# 555_timer.net
KiCad netlist of a schematic drawn in EAGLE
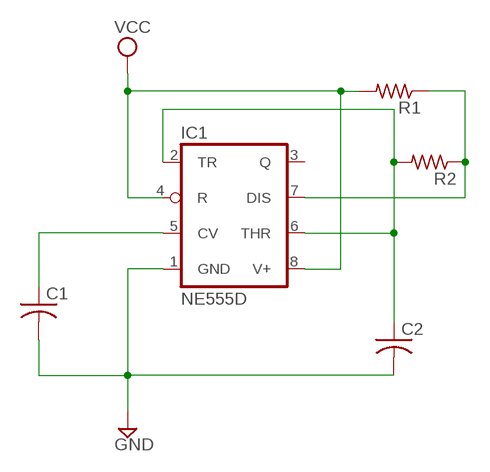
[diagram p0: schematic, sheet 1]

(export (version "E")
  (design (tool "Eeschema 10.0.6"))
  (components
    (comp (ref "C1")
      (value "C-USC0805")
      (footprint "eagle-import:C0805")
      (libsource (lib "eagle-import") (part "C-USC0805"))
    )
    (comp (ref "C2")
      (value "C-USC0805")
      (footprint "eagle-import:C0805")
      (libsource (lib "eagle-import") (part "C-USC0805"))
    )
    (comp (ref "IC1")
      (value "NE555D")
      (footprint "eagle-import:SO08")
      (libsource (lib "eagle-import") (part "555DNE"))
    )
    (comp (ref "R1")
      (value "R-US_R0805")
      (footprint "eagle-import:R0805")
      (libsource (lib "eagle-import") (part "R-US_R0805"))
    )
    (comp (ref "R2")
      (value "R-US_R0805")
      (footprint "eagle-import:R0805")
      (libsource (lib "eagle-import") (part "R-US_R0805"))
    )
  )
  (nets
    (net (code "1") (name "GND") (class "Default")
      (node (ref "C1") (pin "2") (pinfunction "2_2") (pintype "passive"))
      (node (ref "C2") (pin "2") (pinfunction "2_2") (pintype "passive"))
      (node (ref "IC1") (pin "1") (pinfunction "GND_1") (pintype "power_in"))
    )
    (net (code "2") (name "Net-(IC1-CV)") (class "Default")
      (node (ref "C1") (pin "1") (pinfunction "1_1") (pintype "passive"))
      (node (ref "IC1") (pin "5") (pinfunction "CV_5") (pintype "input"))
    )
    (net (code "3") (name "Net-(IC1-DIS)") (class "Default")
      (node (ref "IC1") (pin "7") (pinfunction "DIS_7") (pintype "input"))
      (node (ref "R1") (pin "1") (pinfunction "1_1") (pintype "passive"))
      (node (ref "R2") (pin "1") (pinfunction "1_1") (pintype "passive"))
    )
    (net (code "4") (name "Net-(IC1-THR)") (class "Default")
      (node (ref "C2") (pin "1") (pinfunction "1_1") (pintype "passive"))
      (node (ref "IC1") (pin "2") (pinfunction "TR_2") (pintype "input"))
      (node (ref "IC1") (pin "6") (pinfunction "THR_6") (pintype "input"))
      (node (ref "R2") (pin "2") (pinfunction "2_2") (pintype "passive"))
    )
    (net (code "5") (name "VCC") (class "Default")
      (node (ref "IC1") (pin "4") (pinfunction "R_4") (pintype "input"))
      (node (ref "IC1") (pin "8") (pinfunction "V+_8") (pintype "power_in"))
      (node (ref "R1") (pin "2") (pinfunction "2_2") (pintype "passive"))
    )
    (net (code "6") (name "unconnected-(IC1-Q-Pad3)") (class "Default")
      (node (ref "IC1") (pin "3") (pinfunction "Q_3") (pintype "output"))
    )
  )
)
